# MAIN_AV_Final_2.net
KiCad netlist of a schematic drawn in EAGLE
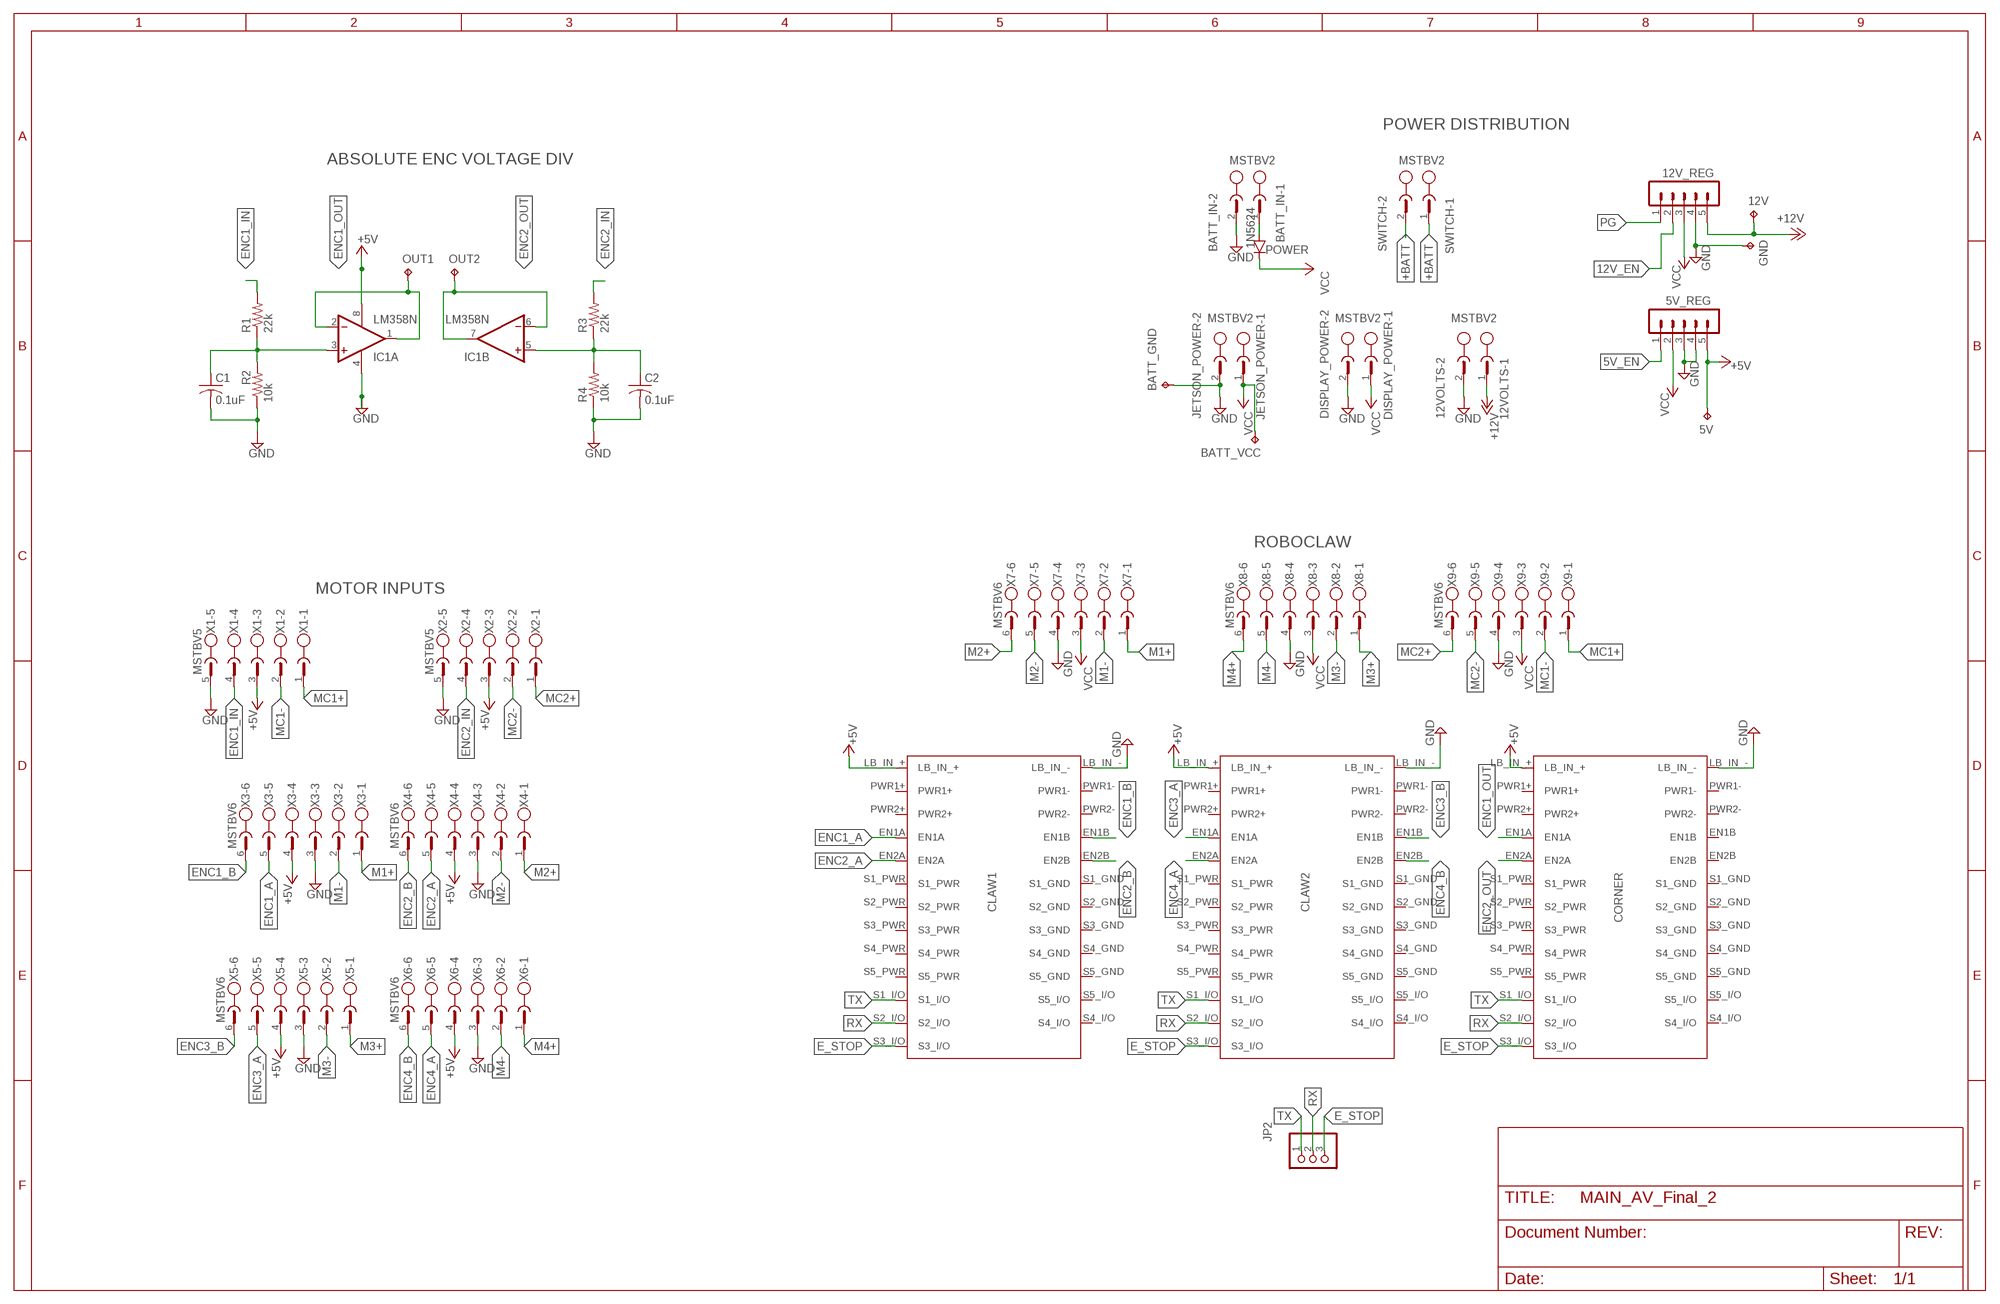
[diagram p0: schematic, sheet 1]

(export (version "E")
  (design (tool "Eeschema 10.0.6"))
  (components
    (comp (ref "5V")
      (value "TPB1,27")
      (footprint "eagle-import:B1,27")
      (libsource (lib "eagle-import") (part "TPB1,27"))
    )
    (comp (ref "5V_REG")
      (value "MA05-1")
      (footprint "eagle-import:MA05-1")
      (libsource (lib "eagle-import") (part "MA05-1"))
    )
    (comp (ref "12V")
      (value "TPB1,27")
      (footprint "eagle-import:B1,27")
      (libsource (lib "eagle-import") (part "TPB1,27"))
    )
    (comp (ref "12VOLTS")
      (value "MSTBV2")
      (footprint "eagle-import:MSTBV2")
      (fields (field (name "MPN") "MSTBV 2,5/2-GF-5.08"))
      (libsource (lib "eagle-import") (part "MSTBV2"))
    )
    (comp (ref "12V_REG")
      (value "MA05-1")
      (footprint "eagle-import:MA05-1")
      (libsource (lib "eagle-import") (part "MA05-1"))
    )
    (comp (ref "BATT_GND")
      (value "TPB1,27")
      (footprint "eagle-import:B1,27")
      (libsource (lib "eagle-import") (part "TPB1,27"))
    )
    (comp (ref "BATT_IN")
      (value "MSTBV2")
      (footprint "eagle-import:MSTBV2")
      (fields (field (name "MPN") "MSTBV 2,5/2-GF-5.08"))
      (libsource (lib "eagle-import") (part "MSTBV2"))
    )
    (comp (ref "BATT_VCC")
      (value "TPB1,27")
      (footprint "eagle-import:B1,27")
      (libsource (lib "eagle-import") (part "TPB1,27"))
    )
    (comp (ref "C1")
      (value "0.1uF")
      (footprint "eagle-import:C050-024X044")
      (libsource (lib "eagle-import") (part "C-US050-024X044"))
    )
    (comp (ref "C2")
      (value "0.1uF")
      (footprint "eagle-import:C050-024X044")
      (libsource (lib "eagle-import") (part "C-US050-024X044"))
    )
    (comp (ref "CLAW1")
      (value "ROBOCLAW2X7A")
      (footprint "eagle-import:ROBOCLAW")
      (libsource (lib "eagle-import") (part "ROBOCLAW2X7A"))
    )
    (comp (ref "CLAW2")
      (value "ROBOCLAW2X7A")
      (footprint "eagle-import:ROBOCLAW")
      (libsource (lib "eagle-import") (part "ROBOCLAW2X7A"))
    )
    (comp (ref "CORNER")
      (value "ROBOCLAW2X7A")
      (footprint "eagle-import:ROBOCLAW")
      (libsource (lib "eagle-import") (part "ROBOCLAW2X7A"))
    )
    (comp (ref "DISPLAY_POWER")
      (value "MSTBV2")
      (footprint "eagle-import:MSTBV2")
      (fields (field (name "MPN") "MSTBV 2,5/2-GF-5.08"))
      (libsource (lib "eagle-import") (part "MSTBV2"))
    )
    (comp (ref "GND")
      (value "TPB1,27")
      (footprint "eagle-import:B1,27")
      (libsource (lib "eagle-import") (part "TPB1,27"))
    )
    (comp (ref "IC1")
      (value "LM358N")
      (footprint "eagle-import:DIL08")
      (libsource (lib "eagle-import") (part "LM358N"))
    )
    (comp (ref "JETSON_POWER")
      (value "MSTBV2")
      (footprint "eagle-import:MSTBV2")
      (fields (field (name "MPN") "MSTBV 2,5/2-GF-5.08"))
      (libsource (lib "eagle-import") (part "MSTBV2"))
    )
    (comp (ref "JP2")
      (value "PINHD-1X3")
      (footprint "eagle-import:1X03")
      (libsource (lib "eagle-import") (part "PINHD-1X3"))
    )
    (comp (ref "OUT1")
      (value "TPB1,27")
      (footprint "eagle-import:B1,27")
      (libsource (lib "eagle-import") (part "TPB1,27"))
    )
    (comp (ref "OUT2")
      (value "TPB1,27")
      (footprint "eagle-import:B1,27")
      (libsource (lib "eagle-import") (part "TPB1,27"))
    )
    (comp (ref "POWER")
      (value "1N5624")
      (footprint "eagle-import:DO201-15")
      (libsource (lib "eagle-import") (part "1N5624"))
    )
    (comp (ref "R1")
      (value "22k")
      (footprint "eagle-import:0204_7")
      (libsource (lib "eagle-import") (part "R-US_0204/7"))
    )
    (comp (ref "R2")
      (value "10k")
      (footprint "eagle-import:0204_7")
      (libsource (lib "eagle-import") (part "R-US_0204/7"))
    )
    (comp (ref "R3")
      (value "22k")
      (footprint "eagle-import:0204_7")
      (libsource (lib "eagle-import") (part "R-US_0204/7"))
    )
    (comp (ref "R4")
      (value "10k")
      (footprint "eagle-import:0204_7")
      (libsource (lib "eagle-import") (part "R-US_0204/7"))
    )
    (comp (ref "SWITCH")
      (value "MSTBV2")
      (footprint "eagle-import:MSTBV2")
      (fields (field (name "MPN") "MSTBV 2,5/2-GF-5.08"))
      (libsource (lib "eagle-import") (part "MSTBV2"))
    )
    (comp (ref "X1")
      (value "MSTBV5")
      (footprint "eagle-import:MSTBV5")
      (fields (field (name "MPN") "MSTBV 2,5/5-GF-5.08"))
      (libsource (lib "eagle-import") (part "MSTBV5"))
    )
    (comp (ref "X2")
      (value "MSTBV5")
      (footprint "eagle-import:MSTBV5")
      (fields (field (name "MPN") "MSTBV 2,5/5-GF-5.08"))
      (libsource (lib "eagle-import") (part "MSTBV5"))
    )
    (comp (ref "X3")
      (value "MSTBV6")
      (footprint "eagle-import:MSTBV6")
      (fields (field (name "MPN") "MSTBV 2,5/6-GF-5.08"))
      (libsource (lib "eagle-import") (part "MSTBV6"))
    )
    (comp (ref "X4")
      (value "MSTBV6")
      (footprint "eagle-import:MSTBV6")
      (fields (field (name "MPN") "MSTBV 2,5/6-GF-5.08"))
      (libsource (lib "eagle-import") (part "MSTBV6"))
    )
    (comp (ref "X5")
      (value "MSTBV6")
      (footprint "eagle-import:MSTBV6")
      (fields (field (name "MPN") "MSTBV 2,5/6-GF-5.08"))
      (libsource (lib "eagle-import") (part "MSTBV6"))
    )
    (comp (ref "X6")
      (value "MSTBV6")
      (footprint "eagle-import:MSTBV6")
      (fields (field (name "MPN") "MSTBV 2,5/6-GF-5.08"))
      (libsource (lib "eagle-import") (part "MSTBV6"))
    )
    (comp (ref "X7")
      (value "MSTBV6")
      (footprint "eagle-import:MSTBV6")
      (fields (field (name "MPN") "MSTBV 2,5/6-GF-5.08"))
      (libsource (lib "eagle-import") (part "MSTBV6"))
    )
    (comp (ref "X8")
      (value "MSTBV6")
      (footprint "eagle-import:MSTBV6")
      (fields (field (name "MPN") "MSTBV 2,5/6-GF-5.08"))
      (libsource (lib "eagle-import") (part "MSTBV6"))
    )
    (comp (ref "X9")
      (value "MSTBV6")
      (footprint "eagle-import:MSTBV6")
      (fields (field (name "MPN") "MSTBV 2,5/6-GF-5.08"))
      (libsource (lib "eagle-import") (part "MSTBV6"))
    )
  )
  (nets
    (net (code "1") (name "+5V") (class "Default")
      (node (ref "5V") (pin "TP") (pinfunction "TP_TP") (pintype "input"))
      (node (ref "5V_REG") (pin "5") (pinfunction "5_5") (pintype "passive"))
      (node (ref "CLAW1") (pin "LB_IN_+") (pinfunction "LB_IN_+_LB_IN_+") (pintype "bidirectional"))
      (node (ref "CLAW2") (pin "LB_IN_+") (pinfunction "LB_IN_+_LB_IN_+") (pintype "bidirectional"))
      (node (ref "CORNER") (pin "LB_IN_+") (pinfunction "LB_IN_+_LB_IN_+") (pintype "bidirectional"))
      (node (ref "IC1") (pin "8") (pinfunction "V+_8") (pintype "power_in"))
      (node (ref "X1") (pin "3") (pinfunction "1_3") (pintype "passive"))
      (node (ref "X2") (pin "3") (pinfunction "1_3") (pintype "passive"))
      (node (ref "X3") (pin "4") (pinfunction "1_4") (pintype "passive"))
      (node (ref "X4") (pin "4") (pinfunction "1_4") (pintype "passive"))
      (node (ref "X5") (pin "4") (pinfunction "1_4") (pintype "passive"))
      (node (ref "X6") (pin "4") (pinfunction "1_4") (pintype "passive"))
    )
    (net (code "2") (name "+12V") (class "Default")
      (node (ref "12V") (pin "TP") (pinfunction "TP_TP") (pintype "input"))
      (node (ref "12VOLTS") (pin "1") (pinfunction "1_1") (pintype "passive"))
      (node (ref "12V_REG") (pin "5") (pinfunction "5_5") (pintype "passive"))
    )
    (net (code "3") (name "+BATT") (class "Default")
      (node (ref "SWITCH") (pin "1") (pinfunction "1_1") (pintype "passive"))
      (node (ref "SWITCH") (pin "2") (pinfunction "1_2") (pintype "passive"))
    )
    (net (code "4") (name "5V_EN") (class "Default")
      (node (ref "5V_REG") (pin "1") (pinfunction "1_1") (pintype "passive"))
    )
    (net (code "5") (name "12V_EN") (class "Default")
      (node (ref "12V_REG") (pin "2") (pinfunction "2_2") (pintype "passive"))
    )
    (net (code "6") (name "ENC1_A") (class "Default")
      (node (ref "CLAW1") (pin "EN1A") (pinfunction "EN1A_EN1A") (pintype "bidirectional"))
      (node (ref "X3") (pin "5") (pinfunction "1_5") (pintype "passive"))
    )
    (net (code "7") (name "ENC1_B") (class "Default")
      (node (ref "CLAW1") (pin "EN1B") (pinfunction "EN1B_EN1B") (pintype "bidirectional"))
      (node (ref "X3") (pin "6") (pinfunction "1_6") (pintype "passive"))
    )
    (net (code "8") (name "ENC1_IN") (class "Default")
      (node (ref "R1") (pin "2") (pinfunction "2_2") (pintype "passive"))
      (node (ref "X1") (pin "4") (pinfunction "1_4") (pintype "passive"))
    )
    (net (code "9") (name "ENC1_OUT") (class "Default")
      (node (ref "CORNER") (pin "EN1A") (pinfunction "EN1A_EN1A") (pintype "bidirectional"))
      (node (ref "IC1") (pin "1") (pinfunction "OUT_1") (pintype "output"))
      (node (ref "IC1") (pin "2") (pinfunction "-IN_2") (pintype "input"))
      (node (ref "OUT1") (pin "TP") (pinfunction "TP_TP") (pintype "input"))
    )
    (net (code "10") (name "ENC2_A") (class "Default")
      (node (ref "CLAW1") (pin "EN2A") (pinfunction "EN2A_EN2A") (pintype "bidirectional"))
      (node (ref "X4") (pin "5") (pinfunction "1_5") (pintype "passive"))
    )
    (net (code "11") (name "ENC2_B") (class "Default")
      (node (ref "CLAW1") (pin "EN2B") (pinfunction "EN2B_EN2B") (pintype "bidirectional"))
      (node (ref "X4") (pin "6") (pinfunction "1_6") (pintype "passive"))
    )
    (net (code "12") (name "ENC2_IN") (class "Default")
      (node (ref "R3") (pin "2") (pinfunction "2_2") (pintype "passive"))
      (node (ref "X2") (pin "4") (pinfunction "1_4") (pintype "passive"))
    )
    (net (code "13") (name "ENC2_OUT") (class "Default")
      (node (ref "CORNER") (pin "EN2A") (pinfunction "EN2A_EN2A") (pintype "bidirectional"))
      (node (ref "IC1") (pin "6") (pinfunction "-IN_6") (pintype "input"))
      (node (ref "IC1") (pin "7") (pinfunction "OUT_7") (pintype "output"))
      (node (ref "OUT2") (pin "TP") (pinfunction "TP_TP") (pintype "input"))
    )
    (net (code "14") (name "ENC3_A") (class "Default")
      (node (ref "CLAW2") (pin "EN1A") (pinfunction "EN1A_EN1A") (pintype "bidirectional"))
      (node (ref "X5") (pin "5") (pinfunction "1_5") (pintype "passive"))
    )
    (net (code "15") (name "ENC3_B") (class "Default")
      (node (ref "CLAW2") (pin "EN1B") (pinfunction "EN1B_EN1B") (pintype "bidirectional"))
      (node (ref "X5") (pin "6") (pinfunction "1_6") (pintype "passive"))
    )
    (net (code "16") (name "ENC4_A") (class "Default")
      (node (ref "CLAW2") (pin "EN2A") (pinfunction "EN2A_EN2A") (pintype "bidirectional"))
      (node (ref "X6") (pin "5") (pinfunction "1_5") (pintype "passive"))
    )
    (net (code "17") (name "ENC4_B") (class "Default")
      (node (ref "CLAW2") (pin "EN2B") (pinfunction "EN2B_EN2B") (pintype "bidirectional"))
      (node (ref "X6") (pin "6") (pinfunction "1_6") (pintype "passive"))
    )
    (net (code "18") (name "E_STOP") (class "Default")
      (node (ref "CLAW1") (pin "S3_I/O") (pinfunction "S3_I/O_S3_I/O") (pintype "bidirectional"))
      (node (ref "CLAW2") (pin "S3_I/O") (pinfunction "S3_I/O_S3_I/O") (pintype "bidirectional"))
      (node (ref "CORNER") (pin "S3_I/O") (pinfunction "S3_I/O_S3_I/O") (pintype "bidirectional"))
      (node (ref "JP2") (pin "3") (pinfunction "3_3") (pintype "passive"))
    )
    (net (code "19") (name "GND") (class "Default")
      (node (ref "12VOLTS") (pin "2") (pinfunction "1_2") (pintype "passive"))
      (node (ref "12V_REG") (pin "4") (pinfunction "4_4") (pintype "passive"))
      (node (ref "5V_REG") (pin "3") (pinfunction "3_3") (pintype "passive"))
      (node (ref "5V_REG") (pin "4") (pinfunction "4_4") (pintype "passive"))
      (node (ref "BATT_GND") (pin "TP") (pinfunction "TP_TP") (pintype "input"))
      (node (ref "BATT_IN") (pin "2") (pinfunction "1_2") (pintype "passive"))
      (node (ref "C1") (pin "2") (pinfunction "2_2") (pintype "passive"))
      (node (ref "C2") (pin "2") (pinfunction "2_2") (pintype "passive"))
      (node (ref "CLAW1") (pin "LB_IN_-") (pinfunction "LB_IN_-_LB_IN_-") (pintype "bidirectional"))
      (node (ref "CLAW2") (pin "LB_IN_-") (pinfunction "LB_IN_-_LB_IN_-") (pintype "bidirectional"))
      (node (ref "CORNER") (pin "LB_IN_-") (pinfunction "LB_IN_-_LB_IN_-") (pintype "bidirectional"))
      (node (ref "DISPLAY_POWER") (pin "2") (pinfunction "1_2") (pintype "passive"))
      (node (ref "GND") (pin "TP") (pinfunction "TP_TP") (pintype "input"))
      (node (ref "IC1") (pin "4") (pinfunction "V-_4") (pintype "power_in"))
      (node (ref "JETSON_POWER") (pin "2") (pinfunction "1_2") (pintype "passive"))
      (node (ref "R2") (pin "1") (pinfunction "1_1") (pintype "passive"))
      (node (ref "R4") (pin "1") (pinfunction "1_1") (pintype "passive"))
      (node (ref "X1") (pin "5") (pinfunction "1_5") (pintype "passive"))
      (node (ref "X2") (pin "5") (pinfunction "1_5") (pintype "passive"))
      (node (ref "X3") (pin "3") (pinfunction "1_3") (pintype "passive"))
      (node (ref "X4") (pin "3") (pinfunction "1_3") (pintype "passive"))
      (node (ref "X5") (pin "3") (pinfunction "1_3") (pintype "passive"))
      (node (ref "X6") (pin "3") (pinfunction "1_3") (pintype "passive"))
      (node (ref "X7") (pin "4") (pinfunction "1_4") (pintype "passive"))
      (node (ref "X8") (pin "4") (pinfunction "1_4") (pintype "passive"))
      (node (ref "X9") (pin "4") (pinfunction "1_4") (pintype "passive"))
    )
    (net (code "20") (name "M1+") (class "Default")
      (node (ref "X3") (pin "1") (pinfunction "1_1") (pintype "passive"))
      (node (ref "X7") (pin "1") (pinfunction "1_1") (pintype "passive"))
    )
    (net (code "21") (name "M1-") (class "Default")
      (node (ref "X3") (pin "2") (pinfunction "1_2") (pintype "passive"))
      (node (ref "X7") (pin "2") (pinfunction "1_2") (pintype "passive"))
    )
    (net (code "22") (name "M2+") (class "Default")
      (node (ref "X4") (pin "1") (pinfunction "1_1") (pintype "passive"))
      (node (ref "X7") (pin "6") (pinfunction "1_6") (pintype "passive"))
    )
    (net (code "23") (name "M2-") (class "Default")
      (node (ref "X4") (pin "2") (pinfunction "1_2") (pintype "passive"))
      (node (ref "X7") (pin "5") (pinfunction "1_5") (pintype "passive"))
    )
    (net (code "24") (name "M3+") (class "Default")
      (node (ref "X5") (pin "1") (pinfunction "1_1") (pintype "passive"))
      (node (ref "X8") (pin "1") (pinfunction "1_1") (pintype "passive"))
    )
    (net (code "25") (name "M3-") (class "Default")
      (node (ref "X5") (pin "2") (pinfunction "1_2") (pintype "passive"))
      (node (ref "X8") (pin "2") (pinfunction "1_2") (pintype "passive"))
    )
    (net (code "26") (name "M4+") (class "Default")
      (node (ref "X6") (pin "1") (pinfunction "1_1") (pintype "passive"))
      (node (ref "X8") (pin "6") (pinfunction "1_6") (pintype "passive"))
    )
    (net (code "27") (name "M4-") (class "Default")
      (node (ref "X6") (pin "2") (pinfunction "1_2") (pintype "passive"))
      (node (ref "X8") (pin "5") (pinfunction "1_5") (pintype "passive"))
    )
    (net (code "28") (name "MC1+") (class "Default")
      (node (ref "X1") (pin "1") (pinfunction "1_1") (pintype "passive"))
      (node (ref "X9") (pin "1") (pinfunction "1_1") (pintype "passive"))
    )
    (net (code "29") (name "MC1-") (class "Default")
      (node (ref "X1") (pin "2") (pinfunction "1_2") (pintype "passive"))
      (node (ref "X9") (pin "2") (pinfunction "1_2") (pintype "passive"))
    )
    (net (code "30") (name "MC2+") (class "Default")
      (node (ref "X2") (pin "1") (pinfunction "1_1") (pintype "passive"))
      (node (ref "X9") (pin "6") (pinfunction "1_6") (pintype "passive"))
    )
    (net (code "31") (name "MC2-") (class "Default")
      (node (ref "X2") (pin "2") (pinfunction "1_2") (pintype "passive"))
      (node (ref "X9") (pin "5") (pinfunction "1_5") (pintype "passive"))
    )
    (net (code "32") (name "Net-(BATT_IN-Pad1)") (class "Default")
      (node (ref "BATT_IN") (pin "1") (pinfunction "1_1") (pintype "passive"))
      (node (ref "POWER") (pin "A") (pinfunction "A_A") (pintype "passive"))
    )
    (net (code "33") (name "Net-(IC1A-+IN)") (class "Default")
      (node (ref "C1") (pin "1") (pinfunction "1_1") (pintype "passive"))
      (node (ref "IC1") (pin "3") (pinfunction "+IN_3") (pintype "input"))
      (node (ref "R1") (pin "1") (pinfunction "1_1") (pintype "passive"))
      (node (ref "R2") (pin "2") (pinfunction "2_2") (pintype "passive"))
    )
    (net (code "34") (name "Net-(IC1B-+IN)") (class "Default")
      (node (ref "C2") (pin "1") (pinfunction "1_1") (pintype "passive"))
      (node (ref "IC1") (pin "5") (pinfunction "+IN_5") (pintype "input"))
      (node (ref "R3") (pin "1") (pinfunction "1_1") (pintype "passive"))
      (node (ref "R4") (pin "2") (pinfunction "2_2") (pintype "passive"))
    )
    (net (code "35") (name "PG") (class "Default")
      (node (ref "12V_REG") (pin "1") (pinfunction "1_1") (pintype "passive"))
    )
    (net (code "36") (name "RX") (class "Default")
      (node (ref "CLAW1") (pin "S2_I/O") (pinfunction "S2_I/O_S2_I/O") (pintype "bidirectional"))
      (node (ref "CLAW2") (pin "S2_I/O") (pinfunction "S2_I/O_S2_I/O") (pintype "bidirectional"))
      (node (ref "CORNER") (pin "S2_I/O") (pinfunction "S2_I/O_S2_I/O") (pintype "bidirectional"))
      (node (ref "JP2") (pin "2") (pinfunction "2_2") (pintype "passive"))
    )
    (net (code "37") (name "TX") (class "Default")
      (node (ref "CLAW1") (pin "S1_I/O") (pinfunction "S1_I/O_S1_I/O") (pintype "bidirectional"))
      (node (ref "CLAW2") (pin "S1_I/O") (pinfunction "S1_I/O_S1_I/O") (pintype "bidirectional"))
      (node (ref "CORNER") (pin "S1_I/O") (pinfunction "S1_I/O_S1_I/O") (pintype "bidirectional"))
      (node (ref "JP2") (pin "1") (pinfunction "1_1") (pintype "passive"))
    )
    (net (code "38") (name "VCC") (class "Default")
      (node (ref "12V_REG") (pin "3") (pinfunction "3_3") (pintype "passive"))
      (node (ref "5V_REG") (pin "2") (pinfunction "2_2") (pintype "passive"))
      (node (ref "BATT_VCC") (pin "TP") (pinfunction "TP_TP") (pintype "input"))
      (node (ref "DISPLAY_POWER") (pin "1") (pinfunction "1_1") (pintype "passive"))
      (node (ref "JETSON_POWER") (pin "1") (pinfunction "1_1") (pintype "passive"))
      (node (ref "POWER") (pin "C") (pinfunction "C_C") (pintype "passive"))
      (node (ref "X7") (pin "3") (pinfunction "1_3") (pintype "passive"))
      (node (ref "X8") (pin "3") (pinfunction "1_3") (pintype "passive"))
      (node (ref "X9") (pin "3") (pinfunction "1_3") (pintype "passive"))
    )
    (net (code "39") (name "unconnected-(CLAW1-PadPWR1+)") (class "Default")
      (node (ref "CLAW1") (pin "PWR1+") (pinfunction "PWR1+_PWR1+") (pintype "bidirectional"))
    )
    (net (code "40") (name "unconnected-(CLAW1-PadPWR1-)") (class "Default")
      (node (ref "CLAW1") (pin "PWR1-") (pinfunction "PWR1-_PWR1-") (pintype "bidirectional"))
    )
    (net (code "41") (name "unconnected-(CLAW1-PadPWR2+)") (class "Default")
      (node (ref "CLAW1") (pin "PWR2+") (pinfunction "PWR2+_PWR2+") (pintype "bidirectional"))
    )
    (net (code "42") (name "unconnected-(CLAW1-PadPWR2-)") (class "Default")
      (node (ref "CLAW1") (pin "PWR2-") (pinfunction "PWR2-_PWR2-") (pintype "bidirectional"))
    )
    (net (code "43") (name "unconnected-(CLAW1-PadS1_GND)") (class "Default")
      (node (ref "CLAW1") (pin "S1_GND") (pinfunction "S1_GND_S1_GND") (pintype "bidirectional"))
    )
    (net (code "44") (name "unconnected-(CLAW1-PadS1_PWR)") (class "Default")
      (node (ref "CLAW1") (pin "S1_PWR") (pinfunction "S1_PWR_S1_PWR") (pintype "bidirectional"))
    )
    (net (code "45") (name "unconnected-(CLAW1-PadS2_GND)") (class "Default")
      (node (ref "CLAW1") (pin "S2_GND") (pinfunction "S2_GND_S2_GND") (pintype "bidirectional"))
    )
    (net (code "46") (name "unconnected-(CLAW1-PadS2_PWR)") (class "Default")
      (node (ref "CLAW1") (pin "S2_PWR") (pinfunction "S2_PWR_S2_PWR") (pintype "bidirectional"))
    )
    (net (code "47") (name "unconnected-(CLAW1-PadS3_GND)") (class "Default")
      (node (ref "CLAW1") (pin "S3_GND") (pinfunction "S3_GND_S3_GND") (pintype "bidirectional"))
    )
    (net (code "48") (name "unconnected-(CLAW1-PadS3_PWR)") (class "Default")
      (node (ref "CLAW1") (pin "S3_PWR") (pinfunction "S3_PWR_S3_PWR") (pintype "bidirectional"))
    )
    (net (code "49") (name "unconnected-(CLAW1-PadS4_GND)") (class "Default")
      (node (ref "CLAW1") (pin "S4_GND") (pinfunction "S4_GND_S4_GND") (pintype "bidirectional"))
    )
    (net (code "50") (name "unconnected-(CLAW1-PadS4_I{slash}O)") (class "Default")
      (node (ref "CLAW1") (pin "S4_I/O") (pinfunction "S4_I/O_S4_I/O") (pintype "bidirectional"))
    )
    (net (code "51") (name "unconnected-(CLAW1-PadS4_PWR)") (class "Default")
      (node (ref "CLAW1") (pin "S4_PWR") (pinfunction "S4_PWR_S4_PWR") (pintype "bidirectional"))
    )
    (net (code "52") (name "unconnected-(CLAW1-PadS5_GND)") (class "Default")
      (node (ref "CLAW1") (pin "S5_GND") (pinfunction "S5_GND_S5_GND") (pintype "bidirectional"))
    )
    (net (code "53") (name "unconnected-(CLAW1-PadS5_I{slash}O)") (class "Default")
      (node (ref "CLAW1") (pin "S5_I/O") (pinfunction "S5_I/O_S5_I/O") (pintype "bidirectional"))
    )
    (net (code "54") (name "unconnected-(CLAW1-PadS5_PWR)") (class "Default")
      (node (ref "CLAW1") (pin "S5_PWR") (pinfunction "S5_PWR_S5_PWR") (pintype "bidirectional"))
    )
    (net (code "55") (name "unconnected-(CLAW2-PadPWR1+)") (class "Default")
      (node (ref "CLAW2") (pin "PWR1+") (pinfunction "PWR1+_PWR1+") (pintype "bidirectional"))
    )
    (net (code "56") (name "unconnected-(CLAW2-PadPWR1-)") (class "Default")
      (node (ref "CLAW2") (pin "PWR1-") (pinfunction "PWR1-_PWR1-") (pintype "bidirectional"))
    )
    (net (code "57") (name "unconnected-(CLAW2-PadPWR2+)") (class "Default")
      (node (ref "CLAW2") (pin "PWR2+") (pinfunction "PWR2+_PWR2+") (pintype "bidirectional"))
    )
    (net (code "58") (name "unconnected-(CLAW2-PadPWR2-)") (class "Default")
      (node (ref "CLAW2") (pin "PWR2-") (pinfunction "PWR2-_PWR2-") (pintype "bidirectional"))
    )
    (net (code "59") (name "unconnected-(CLAW2-PadS1_GND)") (class "Default")
      (node (ref "CLAW2") (pin "S1_GND") (pinfunction "S1_GND_S1_GND") (pintype "bidirectional"))
    )
    (net (code "60") (name "unconnected-(CLAW2-PadS1_PWR)") (class "Default")
      (node (ref "CLAW2") (pin "S1_PWR") (pinfunction "S1_PWR_S1_PWR") (pintype "bidirectional"))
    )
    (net (code "61") (name "unconnected-(CLAW2-PadS2_GND)") (class "Default")
      (node (ref "CLAW2") (pin "S2_GND") (pinfunction "S2_GND_S2_GND") (pintype "bidirectional"))
    )
    (net (code "62") (name "unconnected-(CLAW2-PadS2_PWR)") (class "Default")
      (node (ref "CLAW2") (pin "S2_PWR") (pinfunction "S2_PWR_S2_PWR") (pintype "bidirectional"))
    )
    (net (code "63") (name "unconnected-(CLAW2-PadS3_GND)") (class "Default")
      (node (ref "CLAW2") (pin "S3_GND") (pinfunction "S3_GND_S3_GND") (pintype "bidirectional"))
    )
    (net (code "64") (name "unconnected-(CLAW2-PadS3_PWR)") (class "Default")
      (node (ref "CLAW2") (pin "S3_PWR") (pinfunction "S3_PWR_S3_PWR") (pintype "bidirectional"))
    )
    (net (code "65") (name "unconnected-(CLAW2-PadS4_GND)") (class "Default")
      (node (ref "CLAW2") (pin "S4_GND") (pinfunction "S4_GND_S4_GND") (pintype "bidirectional"))
    )
    (net (code "66") (name "unconnected-(CLAW2-PadS4_I{slash}O)") (class "Default")
      (node (ref "CLAW2") (pin "S4_I/O") (pinfunction "S4_I/O_S4_I/O") (pintype "bidirectional"))
    )
    (net (code "67") (name "unconnected-(CLAW2-PadS4_PWR)") (class "Default")
      (node (ref "CLAW2") (pin "S4_PWR") (pinfunction "S4_PWR_S4_PWR") (pintype "bidirectional"))
    )
    (net (code "68") (name "unconnected-(CLAW2-PadS5_GND)") (class "Default")
      (node (ref "CLAW2") (pin "S5_GND") (pinfunction "S5_GND_S5_GND") (pintype "bidirectional"))
    )
    (net (code "69") (name "unconnected-(CLAW2-PadS5_I{slash}O)") (class "Default")
      (node (ref "CLAW2") (pin "S5_I/O") (pinfunction "S5_I/O_S5_I/O") (pintype "bidirectional"))
    )
    (net (code "70") (name "unconnected-(CLAW2-PadS5_PWR)") (class "Default")
      (node (ref "CLAW2") (pin "S5_PWR") (pinfunction "S5_PWR_S5_PWR") (pintype "bidirectional"))
    )
    (net (code "71") (name "unconnected-(CORNER-PadEN1B)") (class "Default")
      (node (ref "CORNER") (pin "EN1B") (pinfunction "EN1B_EN1B") (pintype "bidirectional"))
    )
    (net (code "72") (name "unconnected-(CORNER-PadEN2B)") (class "Default")
      (node (ref "CORNER") (pin "EN2B") (pinfunction "EN2B_EN2B") (pintype "bidirectional"))
    )
    (net (code "73") (name "unconnected-(CORNER-PadPWR1+)") (class "Default")
      (node (ref "CORNER") (pin "PWR1+") (pinfunction "PWR1+_PWR1+") (pintype "bidirectional"))
    )
    (net (code "74") (name "unconnected-(CORNER-PadPWR1-)") (class "Default")
      (node (ref "CORNER") (pin "PWR1-") (pinfunction "PWR1-_PWR1-") (pintype "bidirectional"))
    )
    (net (code "75") (name "unconnected-(CORNER-PadPWR2+)") (class "Default")
      (node (ref "CORNER") (pin "PWR2+") (pinfunction "PWR2+_PWR2+") (pintype "bidirectional"))
    )
    (net (code "76") (name "unconnected-(CORNER-PadPWR2-)") (class "Default")
      (node (ref "CORNER") (pin "PWR2-") (pinfunction "PWR2-_PWR2-") (pintype "bidirectional"))
    )
    (net (code "77") (name "unconnected-(CORNER-PadS1_GND)") (class "Default")
      (node (ref "CORNER") (pin "S1_GND") (pinfunction "S1_GND_S1_GND") (pintype "bidirectional"))
    )
    (net (code "78") (name "unconnected-(CORNER-PadS1_PWR)") (class "Default")
      (node (ref "CORNER") (pin "S1_PWR") (pinfunction "S1_PWR_S1_PWR") (pintype "bidirectional"))
    )
    (net (code "79") (name "unconnected-(CORNER-PadS2_GND)") (class "Default")
      (node (ref "CORNER") (pin "S2_GND") (pinfunction "S2_GND_S2_GND") (pintype "bidirectional"))
    )
    (net (code "80") (name "unconnected-(CORNER-PadS2_PWR)") (class "Default")
      (node (ref "CORNER") (pin "S2_PWR") (pinfunction "S2_PWR_S2_PWR") (pintype "bidirectional"))
    )
    (net (code "81") (name "unconnected-(CORNER-PadS3_GND)") (class "Default")
      (node (ref "CORNER") (pin "S3_GND") (pinfunction "S3_GND_S3_GND") (pintype "bidirectional"))
    )
    (net (code "82") (name "unconnected-(CORNER-PadS3_PWR)") (class "Default")
      (node (ref "CORNER") (pin "S3_PWR") (pinfunction "S3_PWR_S3_PWR") (pintype "bidirectional"))
    )
    (net (code "83") (name "unconnected-(CORNER-PadS4_GND)") (class "Default")
      (node (ref "CORNER") (pin "S4_GND") (pinfunction "S4_GND_S4_GND") (pintype "bidirectional"))
    )
    (net (code "84") (name "unconnected-(CORNER-PadS4_I{slash}O)") (class "Default")
      (node (ref "CORNER") (pin "S4_I/O") (pinfunction "S4_I/O_S4_I/O") (pintype "bidirectional"))
    )
    (net (code "85") (name "unconnected-(CORNER-PadS4_PWR)") (class "Default")
      (node (ref "CORNER") (pin "S4_PWR") (pinfunction "S4_PWR_S4_PWR") (pintype "bidirectional"))
    )
    (net (code "86") (name "unconnected-(CORNER-PadS5_GND)") (class "Default")
      (node (ref "CORNER") (pin "S5_GND") (pinfunction "S5_GND_S5_GND") (pintype "bidirectional"))
    )
    (net (code "87") (name "unconnected-(CORNER-PadS5_I{slash}O)") (class "Default")
      (node (ref "CORNER") (pin "S5_I/O") (pinfunction "S5_I/O_S5_I/O") (pintype "bidirectional"))
    )
    (net (code "88") (name "unconnected-(CORNER-PadS5_PWR)") (class "Default")
      (node (ref "CORNER") (pin "S5_PWR") (pinfunction "S5_PWR_S5_PWR") (pintype "bidirectional"))
    )
  )
)
